# kumand_v05.net
KiCad netlist of a schematic drawn in EAGLE
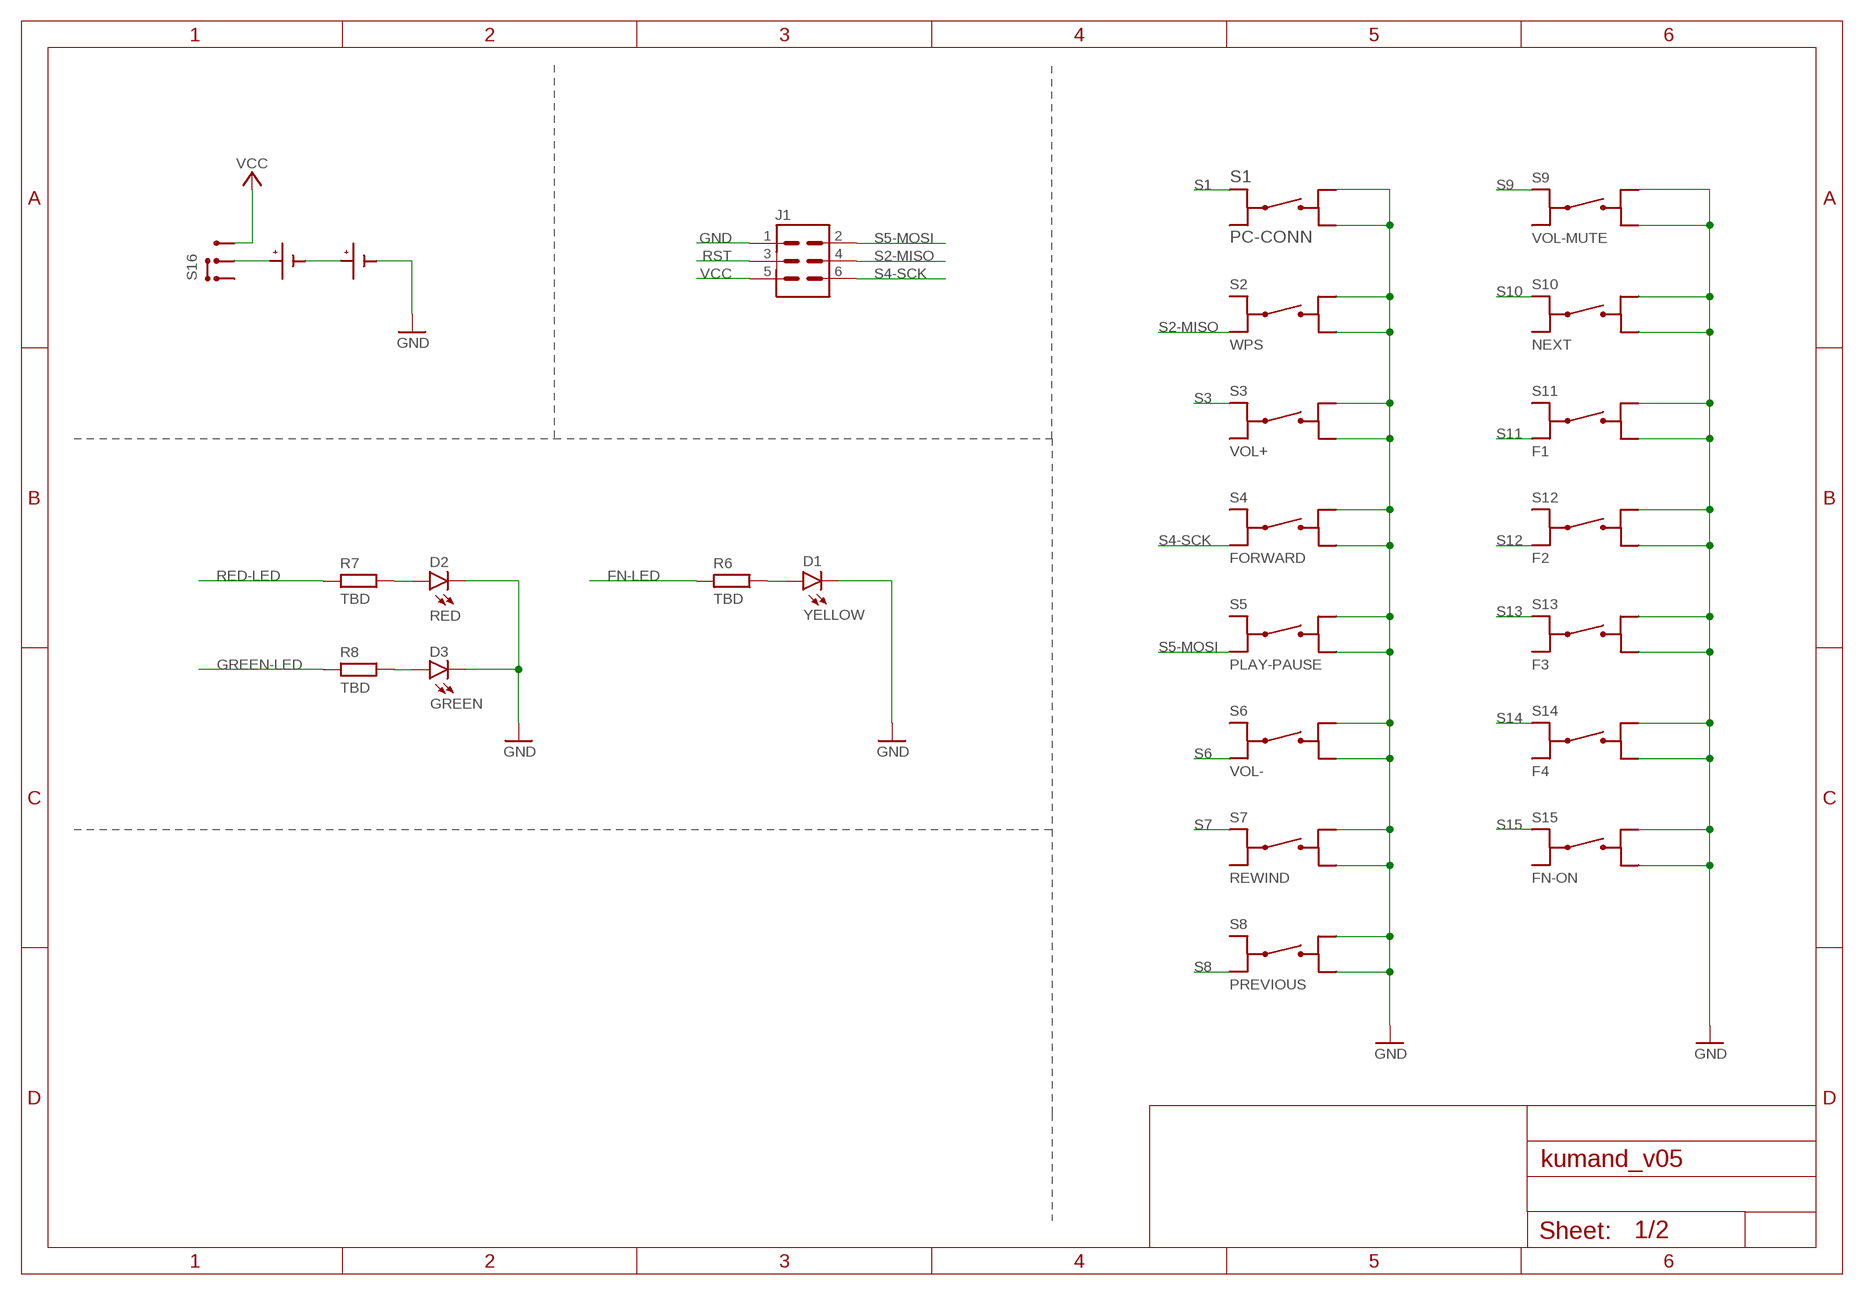
[diagram p0: schematic, sheet 1]
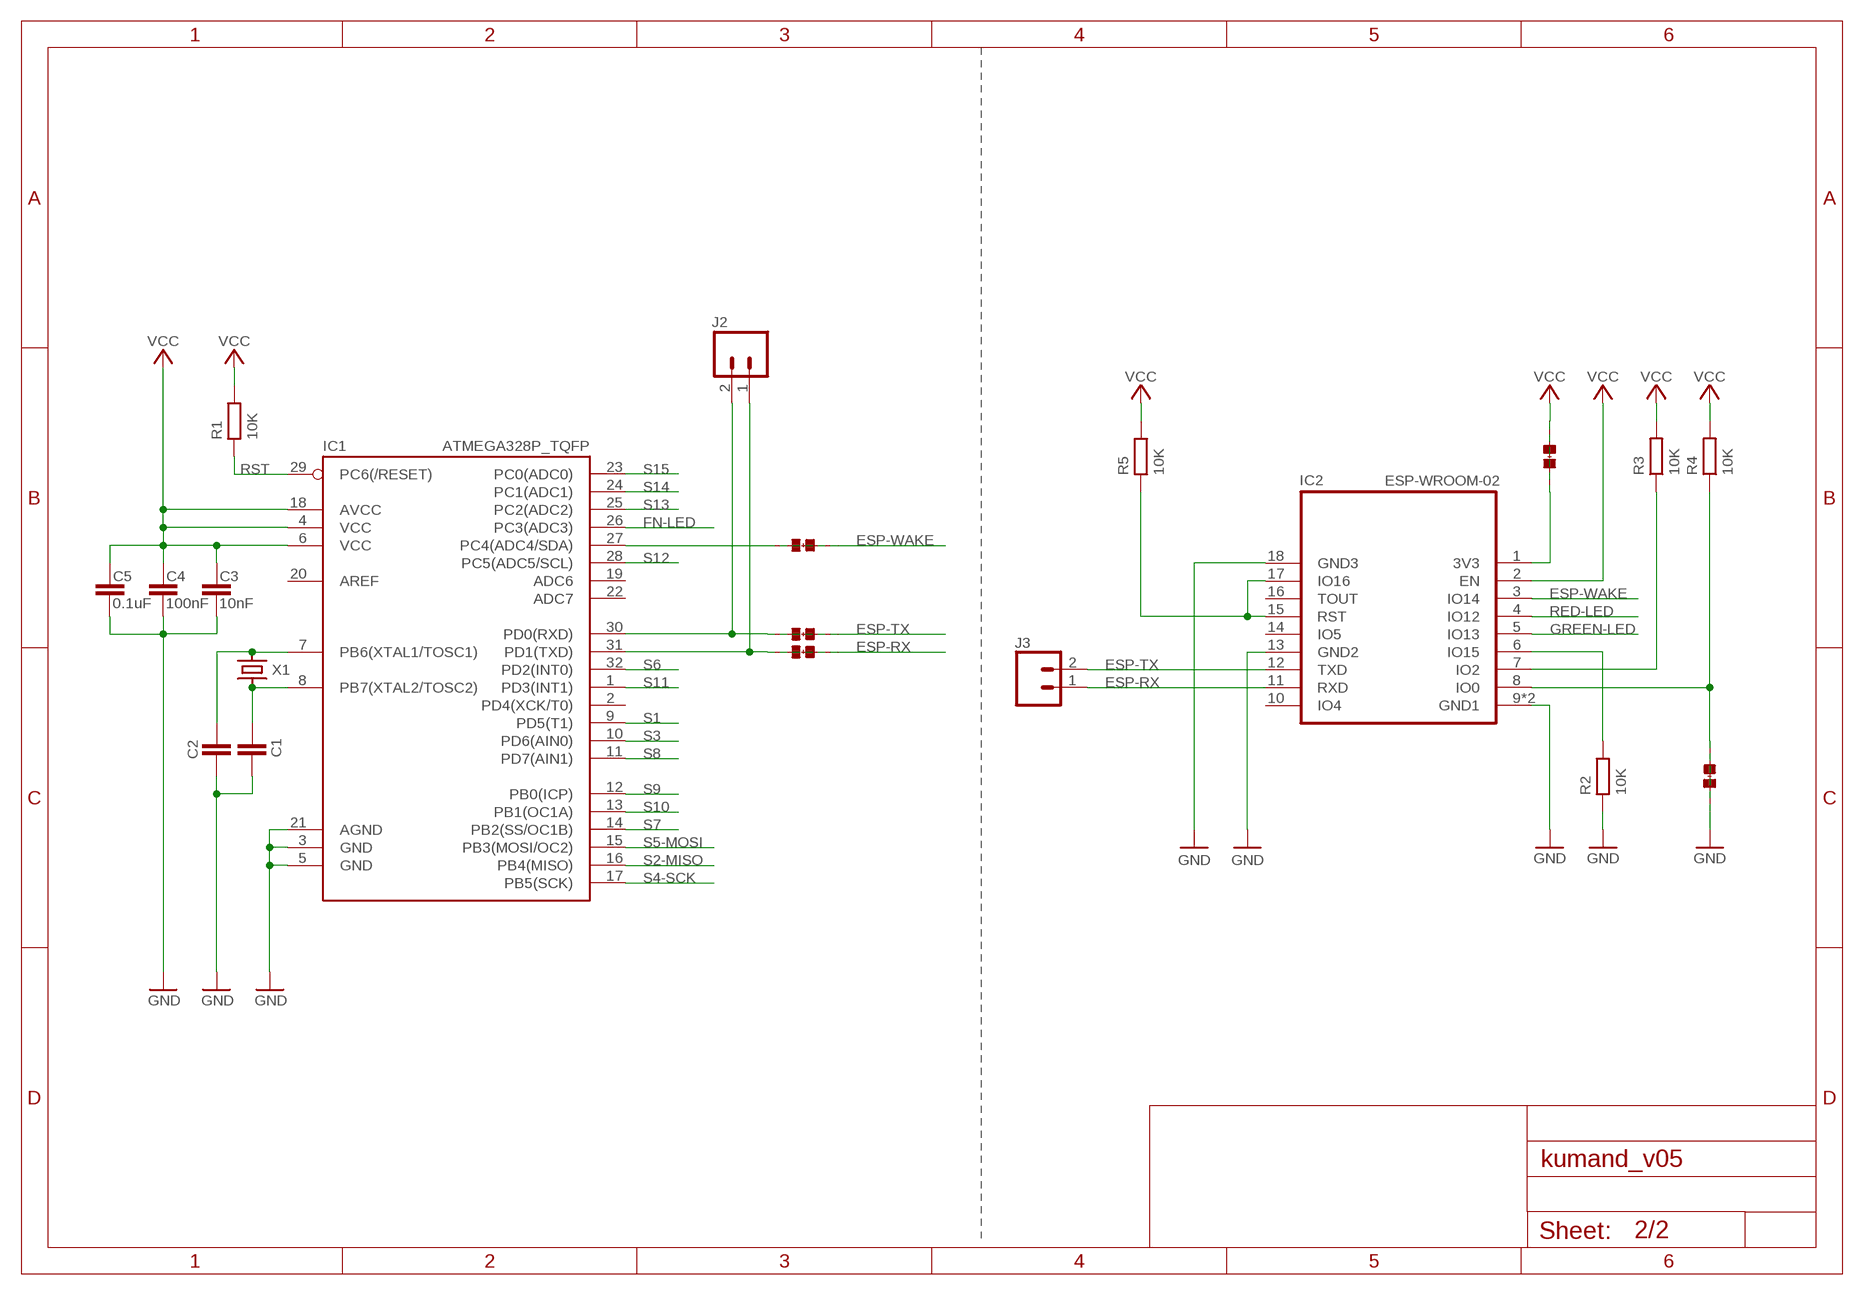
[diagram p1: schematic, sheet 2]

(export (version "E")
  (design (tool "Eeschema 10.0.6"))
  (components
    (comp (ref "D1")
      (value "YELLOW")
      (footprint "eagle-import:LED-1206")
      (libsource (lib "eagle-import") (part "LED1206"))
    )
    (comp (ref "D2")
      (value "RED")
      (footprint "eagle-import:LED-1206")
      (libsource (lib "eagle-import") (part "LED1206"))
    )
    (comp (ref "D3")
      (value "GREEN")
      (footprint "eagle-import:LED-1206")
      (libsource (lib "eagle-import") (part "LED1206"))
    )
    (comp (ref "J1")
      (value "3X2-SMD-DOT")
      (footprint "eagle-import:3X2-SMD-DOT")
      (libsource (lib "eagle-import") (part "3X2-SMD-DOT"))
    )
    (comp (ref "R6")
      (value "TBD")
      (footprint "eagle-import:R1206")
      (libsource (lib "eagle-import") (part "R-EU_R1206"))
    )
    (comp (ref "R7")
      (value "TBD")
      (footprint "eagle-import:R1206")
      (libsource (lib "eagle-import") (part "R-EU_R1206"))
    )
    (comp (ref "R8")
      (value "TBD")
      (footprint "eagle-import:R1206")
      (libsource (lib "eagle-import") (part "R-EU_R1206"))
    )
    (comp (ref "S1")
      (value "PC-CONN")
      (footprint "eagle-import:PTS525")
      (libsource (lib "eagle-import") (part "PTS525"))
    )
    (comp (ref "S2")
      (value "WPS")
      (footprint "eagle-import:PTS525")
      (libsource (lib "eagle-import") (part "PTS525"))
    )
    (comp (ref "S3")
      (value "VOL+")
      (footprint "eagle-import:PTS525")
      (libsource (lib "eagle-import") (part "PTS525"))
    )
    (comp (ref "S4")
      (value "FORWARD")
      (footprint "eagle-import:PTS525")
      (libsource (lib "eagle-import") (part "PTS525"))
    )
    (comp (ref "S5")
      (value "PLAY-PAUSE")
      (footprint "eagle-import:PTS525")
      (libsource (lib "eagle-import") (part "PTS525"))
    )
    (comp (ref "S6")
      (value "VOL-")
      (footprint "eagle-import:PTS525")
      (libsource (lib "eagle-import") (part "PTS525"))
    )
    (comp (ref "S7")
      (value "REWIND")
      (footprint "eagle-import:PTS525")
      (libsource (lib "eagle-import") (part "PTS525"))
    )
    (comp (ref "S8")
      (value "PREVIOUS")
      (footprint "eagle-import:PTS525")
      (libsource (lib "eagle-import") (part "PTS525"))
    )
    (comp (ref "S9")
      (value "VOL-MUTE")
      (footprint "eagle-import:PTS525")
      (libsource (lib "eagle-import") (part "PTS525"))
    )
    (comp (ref "S10")
      (value "NEXT")
      (footprint "eagle-import:PTS525")
      (libsource (lib "eagle-import") (part "PTS525"))
    )
    (comp (ref "S11")
      (value "F1")
      (footprint "eagle-import:PTS525")
      (libsource (lib "eagle-import") (part "PTS525"))
    )
    (comp (ref "S12")
      (value "F2")
      (footprint "eagle-import:PTS525")
      (libsource (lib "eagle-import") (part "PTS525"))
    )
    (comp (ref "S13")
      (value "F3")
      (footprint "eagle-import:PTS525")
      (libsource (lib "eagle-import") (part "PTS525"))
    )
    (comp (ref "S14")
      (value "F4")
      (footprint "eagle-import:PTS525")
      (libsource (lib "eagle-import") (part "PTS525"))
    )
    (comp (ref "S15")
      (value "FN-ON")
      (footprint "eagle-import:PTS525")
      (libsource (lib "eagle-import") (part "PTS525"))
    )
    (comp (ref "S16")
      (value "CL-SB-12B-02T")
      (footprint "eagle-import:CL-SB-12B-02T-PACKAGE")
      (libsource (lib "eagle-import") (part "CL-SB-12B-02T"))
    )
    (comp (ref "U$4")
      (value "BK-82-DEVICE")
      (footprint "eagle-import:BK-82-PACKAGE")
      (libsource (lib "eagle-import") (part "BK-82-DEVICE"))
    )
    (comp (ref "U$5")
      (value "BK-82-DEVICE")
      (footprint "eagle-import:BK-82-PACKAGE")
      (libsource (lib "eagle-import") (part "BK-82-DEVICE"))
    )
    (comp (ref "C1")
      (value "C-EUC1206")
      (footprint "eagle-import:C1206")
      (libsource (lib "eagle-import") (part "C-EUC1206"))
    )
    (comp (ref "C2")
      (value "C-EUC1206")
      (footprint "eagle-import:C1206")
      (libsource (lib "eagle-import") (part "C-EUC1206"))
    )
    (comp (ref "C3")
      (value "10nF")
      (footprint "eagle-import:C1206")
      (libsource (lib "eagle-import") (part "C-EUC1206"))
    )
    (comp (ref "C4")
      (value "100nF")
      (footprint "eagle-import:C1206")
      (libsource (lib "eagle-import") (part "C-EUC1206"))
    )
    (comp (ref "C5")
      (value "0.1uF")
      (footprint "eagle-import:C1206")
      (libsource (lib "eagle-import") (part "C-EUC1206"))
    )
    (comp (ref "IC1")
      (value "ATMEGA328P_TQFP")
      (footprint "eagle-import:TQFP32-08")
      (libsource (lib "eagle-import") (part "ATMEGA328P_TQFP"))
    )
    (comp (ref "IC2")
      (value "ESP-WROOM-02")
      (footprint "eagle-import:FRONT-FACE")
      (libsource (lib "eagle-import") (part "ESP-WROOM-02FRONT-FACE"))
    )
    (comp (ref "J2")
      (value "CONN_02")
      (footprint "eagle-import:1X02")
      (libsource (lib "eagle-import") (part "CONN_02"))
    )
    (comp (ref "J3")
      (value "CONN_02")
      (footprint "eagle-import:1X02")
      (libsource (lib "eagle-import") (part "CONN_02"))
    )
    (comp (ref "PRG")
      (value "SOLDER-JUMPER")
      (footprint "eagle-import:SOLDER-JUMPER-PACKAGE")
      (libsource (lib "eagle-import") (part "SOLDER-JUMPER"))
    )
    (comp (ref "R1")
      (value "10K")
      (footprint "eagle-import:R1206")
      (libsource (lib "eagle-import") (part "resistor_348_R-EU_R1206"))
    )
    (comp (ref "R2")
      (value "10K")
      (footprint "eagle-import:R1206")
      (libsource (lib "eagle-import") (part "R-EU_R1206"))
    )
    (comp (ref "R3")
      (value "10K")
      (footprint "eagle-import:R1206")
      (libsource (lib "eagle-import") (part "R-EU_R1206"))
    )
    (comp (ref "R4")
      (value "10K")
      (footprint "eagle-import:R1206")
      (libsource (lib "eagle-import") (part "R-EU_R1206"))
    )
    (comp (ref "R5")
      (value "10K")
      (footprint "eagle-import:R1206")
      (libsource (lib "eagle-import") (part "R-EU_R1206"))
    )
    (comp (ref "RX")
      (value "SOLDER-JUMPER")
      (footprint "eagle-import:SOLDER-JUMPER-PACKAGE")
      (libsource (lib "eagle-import") (part "SOLDER-JUMPER"))
    )
    (comp (ref "TX")
      (value "SOLDER-JUMPER")
      (footprint "eagle-import:SOLDER-JUMPER-PACKAGE")
      (libsource (lib "eagle-import") (part "SOLDER-JUMPER"))
    )
    (comp (ref "VCC")
      (value "SOLDER-JUMPER")
      (footprint "eagle-import:SOLDER-JUMPER-PACKAGE")
      (libsource (lib "eagle-import") (part "SOLDER-JUMPER"))
    )
    (comp (ref "WAKE")
      (value "SOLDER-JUMPER")
      (footprint "eagle-import:SOLDER-JUMPER-PACKAGE")
      (libsource (lib "eagle-import") (part "SOLDER-JUMPER"))
    )
    (comp (ref "X1")
      (value "NX8045-CRYSTAL")
      (footprint "eagle-import:NX8045")
      (libsource (lib "eagle-import") (part "NX8045-CRYSTAL"))
    )
  )
  (nets
    (net (code "1") (name "ESP-RX") (class "Default")
      (node (ref "IC2") (pin "11") (pinfunction "RXD_11") (pintype "bidirectional"))
      (node (ref "J3") (pin "1") (pinfunction "1_1") (pintype "passive"))
      (node (ref "RX") (pin "2") (pinfunction "P$2_2") (pintype "bidirectional"))
    )
    (net (code "2") (name "ESP-TX") (class "Default")
      (node (ref "IC2") (pin "12") (pinfunction "TXD_12") (pintype "bidirectional"))
      (node (ref "J3") (pin "2") (pinfunction "2_2") (pintype "passive"))
      (node (ref "TX") (pin "2") (pinfunction "P$2_2") (pintype "bidirectional"))
    )
    (net (code "3") (name "ESP-WAKE") (class "Default")
      (node (ref "IC2") (pin "3") (pinfunction "IO14_3") (pintype "bidirectional"))
      (node (ref "WAKE") (pin "2") (pinfunction "P$2_2") (pintype "bidirectional"))
    )
    (net (code "4") (name "FN-LED") (class "Default")
      (node (ref "IC1") (pin "26") (pinfunction "PC3(ADC3)_26") (pintype "bidirectional"))
      (node (ref "R6") (pin "2") (pinfunction "2_2") (pintype "passive"))
    )
    (net (code "5") (name "GND") (class "Default")
      (node (ref "C1") (pin "1") (pinfunction "1_1") (pintype "passive"))
      (node (ref "C2") (pin "1") (pinfunction "1_1") (pintype "passive"))
      (node (ref "C3") (pin "1") (pinfunction "1_1") (pintype "passive"))
      (node (ref "C4") (pin "1") (pinfunction "1_1") (pintype "passive"))
      (node (ref "C5") (pin "1") (pinfunction "1_1") (pintype "passive"))
      (node (ref "D1") (pin "C") (pinfunction "C_C") (pintype "passive"))
      (node (ref "D2") (pin "C") (pinfunction "C_C") (pintype "passive"))
      (node (ref "D3") (pin "C") (pinfunction "C_C") (pintype "passive"))
      (node (ref "IC1") (pin "21") (pinfunction "AGND_21") (pintype "bidirectional"))
      (node (ref "IC1") (pin "3") (pinfunction "GND_3") (pintype "bidirectional"))
      (node (ref "IC1") (pin "5") (pinfunction "GND_5") (pintype "bidirectional"))
      (node (ref "IC2") (pin "13") (pinfunction "GND2_13") (pintype "power_in"))
      (node (ref "IC2") (pin "18") (pinfunction "GND3_18") (pintype "power_in"))
      (node (ref "IC2") (pin "9") (pinfunction "GND1_9") (pintype "power_in"))
      (node (ref "IC2") (pin "GND") (pinfunction "GND1_GND") (pintype "power_in"))
      (node (ref "J1") (pin "1") (pinfunction "P$1_1") (pintype "bidirectional"))
      (node (ref "PRG") (pin "2") (pinfunction "P$2_2") (pintype "bidirectional"))
      (node (ref "R2") (pin "2") (pinfunction "2_2") (pintype "passive"))
      (node (ref "S1") (pin "3") (pinfunction "P$3_3") (pintype "bidirectional"))
      (node (ref "S1") (pin "4") (pinfunction "P$4_4") (pintype "bidirectional"))
      (node (ref "S10") (pin "3") (pinfunction "P$3_3") (pintype "bidirectional"))
      (node (ref "S10") (pin "4") (pinfunction "P$4_4") (pintype "bidirectional"))
      (node (ref "S11") (pin "3") (pinfunction "P$3_3") (pintype "bidirectional"))
      (node (ref "S11") (pin "4") (pinfunction "P$4_4") (pintype "bidirectional"))
      (node (ref "S12") (pin "3") (pinfunction "P$3_3") (pintype "bidirectional"))
      (node (ref "S12") (pin "4") (pinfunction "P$4_4") (pintype "bidirectional"))
      (node (ref "S13") (pin "3") (pinfunction "P$3_3") (pintype "bidirectional"))
      (node (ref "S13") (pin "4") (pinfunction "P$4_4") (pintype "bidirectional"))
      (node (ref "S14") (pin "3") (pinfunction "P$3_3") (pintype "bidirectional"))
      (node (ref "S14") (pin "4") (pinfunction "P$4_4") (pintype "bidirectional"))
      (node (ref "S15") (pin "3") (pinfunction "P$3_3") (pintype "bidirectional"))
      (node (ref "S15") (pin "4") (pinfunction "P$4_4") (pintype "bidirectional"))
      (node (ref "S2") (pin "3") (pinfunction "P$3_3") (pintype "bidirectional"))
      (node (ref "S2") (pin "4") (pinfunction "P$4_4") (pintype "bidirectional"))
      (node (ref "S3") (pin "3") (pinfunction "P$3_3") (pintype "bidirectional"))
      (node (ref "S3") (pin "4") (pinfunction "P$4_4") (pintype "bidirectional"))
      (node (ref "S4") (pin "3") (pinfunction "P$3_3") (pintype "bidirectional"))
      (node (ref "S4") (pin "4") (pinfunction "P$4_4") (pintype "bidirectional"))
      (node (ref "S5") (pin "3") (pinfunction "P$3_3") (pintype "bidirectional"))
      (node (ref "S5") (pin "4") (pinfunction "P$4_4") (pintype "bidirectional"))
      (node (ref "S6") (pin "3") (pinfunction "P$3_3") (pintype "bidirectional"))
      (node (ref "S6") (pin "4") (pinfunction "P$4_4") (pintype "bidirectional"))
      (node (ref "S7") (pin "3") (pinfunction "P$3_3") (pintype "bidirectional"))
      (node (ref "S7") (pin "4") (pinfunction "P$4_4") (pintype "bidirectional"))
      (node (ref "S8") (pin "3") (pinfunction "P$3_3") (pintype "bidirectional"))
      (node (ref "S8") (pin "4") (pinfunction "P$4_4") (pintype "bidirectional"))
      (node (ref "S9") (pin "3") (pinfunction "P$3_3") (pintype "bidirectional"))
      (node (ref "S9") (pin "4") (pinfunction "P$4_4") (pintype "bidirectional"))
      (node (ref "U$5") (pin "P$2") (pinfunction "P$2_P$2") (pintype "bidirectional"))
      (node (ref "U$5") (pin "P$4") (pinfunction "P$2_P$4") (pintype "bidirectional"))
    )
    (net (code "6") (name "GREEN-LED") (class "Default")
      (node (ref "IC2") (pin "5") (pinfunction "IO13_5") (pintype "bidirectional"))
      (node (ref "R8") (pin "2") (pinfunction "2_2") (pintype "passive"))
    )
    (net (code "7") (name "Net-(D1-PadA)") (class "Default")
      (node (ref "D1") (pin "A") (pinfunction "A_A") (pintype "passive"))
      (node (ref "R6") (pin "1") (pinfunction "1_1") (pintype "passive"))
    )
    (net (code "8") (name "Net-(D2-PadA)") (class "Default")
      (node (ref "D2") (pin "A") (pinfunction "A_A") (pintype "passive"))
      (node (ref "R7") (pin "1") (pinfunction "1_1") (pintype "passive"))
    )
    (net (code "9") (name "Net-(D3-PadA)") (class "Default")
      (node (ref "D3") (pin "A") (pinfunction "A_A") (pintype "passive"))
      (node (ref "R8") (pin "1") (pinfunction "1_1") (pintype "passive"))
    )
    (net (code "10") (name "Net-(IC1-PB6(XTAL1{slash}TOSC1))") (class "Default")
      (node (ref "C2") (pin "2") (pinfunction "2_2") (pintype "passive"))
      (node (ref "IC1") (pin "7") (pinfunction "PB6(XTAL1/TOSC1)_7") (pintype "bidirectional"))
      (node (ref "X1") (pin "P$2") (pinfunction "P$2_P$2") (pintype "passive"))
    )
    (net (code "11") (name "Net-(IC1-PB7(XTAL2{slash}TOSC2))") (class "Default")
      (node (ref "C1") (pin "2") (pinfunction "2_2") (pintype "passive"))
      (node (ref "IC1") (pin "8") (pinfunction "PB7(XTAL2/TOSC2)_8") (pintype "bidirectional"))
      (node (ref "X1") (pin "P$1") (pinfunction "P$1_P$1") (pintype "passive"))
    )
    (net (code "12") (name "Net-(IC1-PC4(ADC4{slash}SDA))") (class "Default")
      (node (ref "IC1") (pin "27") (pinfunction "PC4(ADC4/SDA)_27") (pintype "bidirectional"))
      (node (ref "WAKE") (pin "1") (pinfunction "P$1_1") (pintype "bidirectional"))
    )
    (net (code "13") (name "Net-(IC1-PD0(RXD))") (class "Default")
      (node (ref "IC1") (pin "30") (pinfunction "PD0(RXD)_30") (pintype "bidirectional"))
      (node (ref "J2") (pin "2") (pinfunction "2_2") (pintype "passive"))
      (node (ref "TX") (pin "1") (pinfunction "P$1_1") (pintype "bidirectional"))
    )
    (net (code "14") (name "Net-(IC1-PD1(TXD))") (class "Default")
      (node (ref "IC1") (pin "31") (pinfunction "PD1(TXD)_31") (pintype "bidirectional"))
      (node (ref "J2") (pin "1") (pinfunction "1_1") (pintype "passive"))
      (node (ref "RX") (pin "1") (pinfunction "P$1_1") (pintype "bidirectional"))
    )
    (net (code "15") (name "Net-(IC2-IO0)") (class "Default")
      (node (ref "IC2") (pin "8") (pinfunction "IO0_8") (pintype "bidirectional"))
      (node (ref "PRG") (pin "1") (pinfunction "P$1_1") (pintype "bidirectional"))
      (node (ref "R4") (pin "1") (pinfunction "1_1") (pintype "passive"))
    )
    (net (code "16") (name "Net-(IC2-IO2)") (class "Default")
      (node (ref "IC2") (pin "7") (pinfunction "IO2_7") (pintype "bidirectional"))
      (node (ref "R3") (pin "1") (pinfunction "1_1") (pintype "passive"))
    )
    (net (code "17") (name "Net-(IC2-IO15)") (class "Default")
      (node (ref "IC2") (pin "6") (pinfunction "IO15_6") (pintype "bidirectional"))
      (node (ref "R2") (pin "1") (pinfunction "1_1") (pintype "passive"))
    )
    (net (code "18") (name "Net-(IC2-IO16)") (class "Default")
      (node (ref "IC2") (pin "15") (pinfunction "RST_15") (pintype "bidirectional"))
      (node (ref "IC2") (pin "17") (pinfunction "IO16_17") (pintype "bidirectional"))
      (node (ref "R5") (pin "2") (pinfunction "2_2") (pintype "passive"))
    )
    (net (code "19") (name "Net-(S16-PadP$2)") (class "Default")
      (node (ref "S16") (pin "P$2") (pinfunction "P$2_P$2") (pintype "bidirectional"))
      (node (ref "U$4") (pin "P$1") (pinfunction "P$1_P$1") (pintype "bidirectional"))
      (node (ref "U$4") (pin "P$3") (pinfunction "P$1_P$3") (pintype "bidirectional"))
    )
    (net (code "20") (name "Net-(U$4-P$2-PadP$4)") (class "Default")
      (node (ref "U$4") (pin "P$2") (pinfunction "P$2_P$2") (pintype "bidirectional"))
      (node (ref "U$4") (pin "P$4") (pinfunction "P$2_P$4") (pintype "bidirectional"))
      (node (ref "U$5") (pin "P$1") (pinfunction "P$1_P$1") (pintype "bidirectional"))
      (node (ref "U$5") (pin "P$3") (pinfunction "P$1_P$3") (pintype "bidirectional"))
    )
    (net (code "21") (name "RED-LED") (class "Default")
      (node (ref "IC2") (pin "4") (pinfunction "IO12_4") (pintype "bidirectional"))
      (node (ref "R7") (pin "2") (pinfunction "2_2") (pintype "passive"))
    )
    (net (code "22") (name "RST") (class "Default")
      (node (ref "IC1") (pin "29") (pinfunction "PC6(/RESET)_29") (pintype "bidirectional"))
      (node (ref "J1") (pin "3") (pinfunction "P$3_3") (pintype "bidirectional"))
      (node (ref "R1") (pin "2") (pinfunction "2_2") (pintype "passive"))
    )
    (net (code "23") (name "S1") (class "Default")
      (node (ref "IC1") (pin "9") (pinfunction "PD5(T1)_9") (pintype "bidirectional"))
      (node (ref "S1") (pin "1") (pinfunction "P$1_1") (pintype "bidirectional"))
    )
    (net (code "24") (name "S2-MISO") (class "Default")
      (node (ref "IC1") (pin "16") (pinfunction "PB4(MISO)_16") (pintype "bidirectional"))
      (node (ref "J1") (pin "4") (pinfunction "P$4_4") (pintype "bidirectional"))
      (node (ref "S2") (pin "2") (pinfunction "P$2_2") (pintype "bidirectional"))
    )
    (net (code "25") (name "S3") (class "Default")
      (node (ref "IC1") (pin "10") (pinfunction "PD6(AIN0)_10") (pintype "bidirectional"))
      (node (ref "S3") (pin "1") (pinfunction "P$1_1") (pintype "bidirectional"))
    )
    (net (code "26") (name "S4-SCK") (class "Default")
      (node (ref "IC1") (pin "17") (pinfunction "PB5(SCK)_17") (pintype "bidirectional"))
      (node (ref "J1") (pin "6") (pinfunction "P$6_6") (pintype "bidirectional"))
      (node (ref "S4") (pin "2") (pinfunction "P$2_2") (pintype "bidirectional"))
    )
    (net (code "27") (name "S5-MOSI") (class "Default")
      (node (ref "IC1") (pin "15") (pinfunction "PB3(MOSI/OC2)_15") (pintype "bidirectional"))
      (node (ref "J1") (pin "2") (pinfunction "P$2_2") (pintype "bidirectional"))
      (node (ref "S5") (pin "2") (pinfunction "P$2_2") (pintype "bidirectional"))
    )
    (net (code "28") (name "S6") (class "Default")
      (node (ref "IC1") (pin "32") (pinfunction "PD2(INT0)_32") (pintype "bidirectional"))
      (node (ref "S6") (pin "2") (pinfunction "P$2_2") (pintype "bidirectional"))
    )
    (net (code "29") (name "S7") (class "Default")
      (node (ref "IC1") (pin "14") (pinfunction "PB2(SS/OC1B)_14") (pintype "bidirectional"))
      (node (ref "S7") (pin "1") (pinfunction "P$1_1") (pintype "bidirectional"))
    )
    (net (code "30") (name "S8") (class "Default")
      (node (ref "IC1") (pin "11") (pinfunction "PD7(AIN1)_11") (pintype "bidirectional"))
      (node (ref "S8") (pin "2") (pinfunction "P$2_2") (pintype "bidirectional"))
    )
    (net (code "31") (name "S9") (class "Default")
      (node (ref "IC1") (pin "12") (pinfunction "PB0(ICP)_12") (pintype "bidirectional"))
      (node (ref "S9") (pin "1") (pinfunction "P$1_1") (pintype "bidirectional"))
    )
    (net (code "32") (name "S10") (class "Default")
      (node (ref "IC1") (pin "13") (pinfunction "PB1(OC1A)_13") (pintype "bidirectional"))
      (node (ref "S10") (pin "1") (pinfunction "P$1_1") (pintype "bidirectional"))
    )
    (net (code "33") (name "S11") (class "Default")
      (node (ref "IC1") (pin "1") (pinfunction "PD3(INT1)_1") (pintype "bidirectional"))
      (node (ref "S11") (pin "2") (pinfunction "P$2_2") (pintype "bidirectional"))
    )
    (net (code "34") (name "S12") (class "Default")
      (node (ref "IC1") (pin "28") (pinfunction "PC5(ADC5/SCL)_28") (pintype "bidirectional"))
      (node (ref "S12") (pin "2") (pinfunction "P$2_2") (pintype "bidirectional"))
    )
    (net (code "35") (name "S13") (class "Default")
      (node (ref "IC1") (pin "25") (pinfunction "PC2(ADC2)_25") (pintype "bidirectional"))
      (node (ref "S13") (pin "1") (pinfunction "P$1_1") (pintype "bidirectional"))
    )
    (net (code "36") (name "S14") (class "Default")
      (node (ref "IC1") (pin "24") (pinfunction "PC1(ADC1)_24") (pintype "bidirectional"))
      (node (ref "S14") (pin "1") (pinfunction "P$1_1") (pintype "bidirectional"))
    )
    (net (code "37") (name "S15") (class "Default")
      (node (ref "IC1") (pin "23") (pinfunction "PC0(ADC0)_23") (pintype "bidirectional"))
      (node (ref "S15") (pin "1") (pinfunction "P$1_1") (pintype "bidirectional"))
    )
    (net (code "38") (name "VCC") (class "Default")
      (node (ref "C3") (pin "2") (pinfunction "2_2") (pintype "passive"))
      (node (ref "C4") (pin "2") (pinfunction "2_2") (pintype "passive"))
      (node (ref "C5") (pin "2") (pinfunction "2_2") (pintype "passive"))
      (node (ref "IC1") (pin "18") (pinfunction "AVCC_18") (pintype "bidirectional"))
      (node (ref "IC1") (pin "4") (pinfunction "VCC_4") (pintype "bidirectional"))
      (node (ref "IC1") (pin "6") (pinfunction "VCC_6") (pintype "bidirectional"))
      (node (ref "IC2") (pin "1") (pinfunction "3V3_1") (pintype "power_in"))
      (node (ref "IC2") (pin "2") (pinfunction "EN_2") (pintype "bidirectional"))
      (node (ref "J1") (pin "5") (pinfunction "P$5_5") (pintype "bidirectional"))
      (node (ref "R1") (pin "1") (pinfunction "1_1") (pintype "passive"))
      (node (ref "R3") (pin "2") (pinfunction "2_2") (pintype "passive"))
      (node (ref "R4") (pin "2") (pinfunction "2_2") (pintype "passive"))
      (node (ref "R5") (pin "1") (pinfunction "1_1") (pintype "passive"))
      (node (ref "S16") (pin "P$3") (pinfunction "P$3_P$3") (pintype "bidirectional"))
      (node (ref "VCC") (pin "1") (pinfunction "P$1_1") (pintype "bidirectional"))
      (node (ref "VCC") (pin "2") (pinfunction "P$2_2") (pintype "bidirectional"))
    )
    (net (code "39") (name "unconnected-(IC1-ADC6-Pad19)") (class "Default")
      (node (ref "IC1") (pin "19") (pinfunction "ADC6_19") (pintype "bidirectional"))
    )
    (net (code "40") (name "unconnected-(IC1-ADC7-Pad22)") (class "Default")
      (node (ref "IC1") (pin "22") (pinfunction "ADC7_22") (pintype "bidirectional"))
    )
    (net (code "41") (name "unconnected-(IC1-AREF-Pad20)") (class "Default")
      (node (ref "IC1") (pin "20") (pinfunction "AREF_20") (pintype "bidirectional"))
    )
    (net (code "42") (name "unconnected-(IC1-PD4(XCK{slash}T0)-Pad2)") (class "Default")
      (node (ref "IC1") (pin "2") (pinfunction "PD4(XCK/T0)_2") (pintype "bidirectional"))
    )
    (net (code "43") (name "unconnected-(IC2-IO4-Pad10)") (class "Default")
      (node (ref "IC2") (pin "10") (pinfunction "IO4_10") (pintype "bidirectional"))
    )
    (net (code "44") (name "unconnected-(IC2-IO5-Pad14)") (class "Default")
      (node (ref "IC2") (pin "14") (pinfunction "IO5_14") (pintype "open_collector"))
    )
    (net (code "45") (name "unconnected-(IC2-TOUT-Pad16)") (class "Default")
      (node (ref "IC2") (pin "16") (pinfunction "TOUT_16") (pintype "bidirectional"))
    )
    (net (code "46") (name "unconnected-(S1-P$2-Pad2)") (class "Default")
      (node (ref "S1") (pin "2") (pinfunction "P$2_2") (pintype "bidirectional"))
    )
    (net (code "47") (name "unconnected-(S2-P$1-Pad1)") (class "Default")
      (node (ref "S2") (pin "1") (pinfunction "P$1_1") (pintype "bidirectional"))
    )
    (net (code "48") (name "unconnected-(S3-P$2-Pad2)") (class "Default")
      (node (ref "S3") (pin "2") (pinfunction "P$2_2") (pintype "bidirectional"))
    )
    (net (code "49") (name "unconnected-(S4-P$1-Pad1)") (class "Default")
      (node (ref "S4") (pin "1") (pinfunction "P$1_1") (pintype "bidirectional"))
    )
    (net (code "50") (name "unconnected-(S5-P$1-Pad1)") (class "Default")
      (node (ref "S5") (pin "1") (pinfunction "P$1_1") (pintype "bidirectional"))
    )
    (net (code "51") (name "unconnected-(S6-P$1-Pad1)") (class "Default")
      (node (ref "S6") (pin "1") (pinfunction "P$1_1") (pintype "bidirectional"))
    )
    (net (code "52") (name "unconnected-(S7-P$2-Pad2)") (class "Default")
      (node (ref "S7") (pin "2") (pinfunction "P$2_2") (pintype "bidirectional"))
    )
    (net (code "53") (name "unconnected-(S8-P$1-Pad1)") (class "Default")
      (node (ref "S8") (pin "1") (pinfunction "P$1_1") (pintype "bidirectional"))
    )
    (net (code "54") (name "unconnected-(S9-P$2-Pad2)") (class "Default")
      (node (ref "S9") (pin "2") (pinfunction "P$2_2") (pintype "bidirectional"))
    )
    (net (code "55") (name "unconnected-(S10-P$2-Pad2)") (class "Default")
      (node (ref "S10") (pin "2") (pinfunction "P$2_2") (pintype "bidirectional"))
    )
    (net (code "56") (name "unconnected-(S11-P$1-Pad1)") (class "Default")
      (node (ref "S11") (pin "1") (pinfunction "P$1_1") (pintype "bidirectional"))
    )
    (net (code "57") (name "unconnected-(S12-P$1-Pad1)") (class "Default")
      (node (ref "S12") (pin "1") (pinfunction "P$1_1") (pintype "bidirectional"))
    )
    (net (code "58") (name "unconnected-(S13-P$2-Pad2)") (class "Default")
      (node (ref "S13") (pin "2") (pinfunction "P$2_2") (pintype "bidirectional"))
    )
    (net (code "59") (name "unconnected-(S14-P$2-Pad2)") (class "Default")
      (node (ref "S14") (pin "2") (pinfunction "P$2_2") (pintype "bidirectional"))
    )
    (net (code "60") (name "unconnected-(S15-P$2-Pad2)") (class "Default")
      (node (ref "S15") (pin "2") (pinfunction "P$2_2") (pintype "bidirectional"))
    )
    (net (code "61") (name "unconnected-(S16-PadP$1)") (class "Default")
      (node (ref "S16") (pin "P$1") (pinfunction "P$1_P$1") (pintype "bidirectional"))
    )
  )
)
